# Adafruit_EZ-SFX_with_Amp.net
KiCad netlist of a schematic drawn in EAGLE
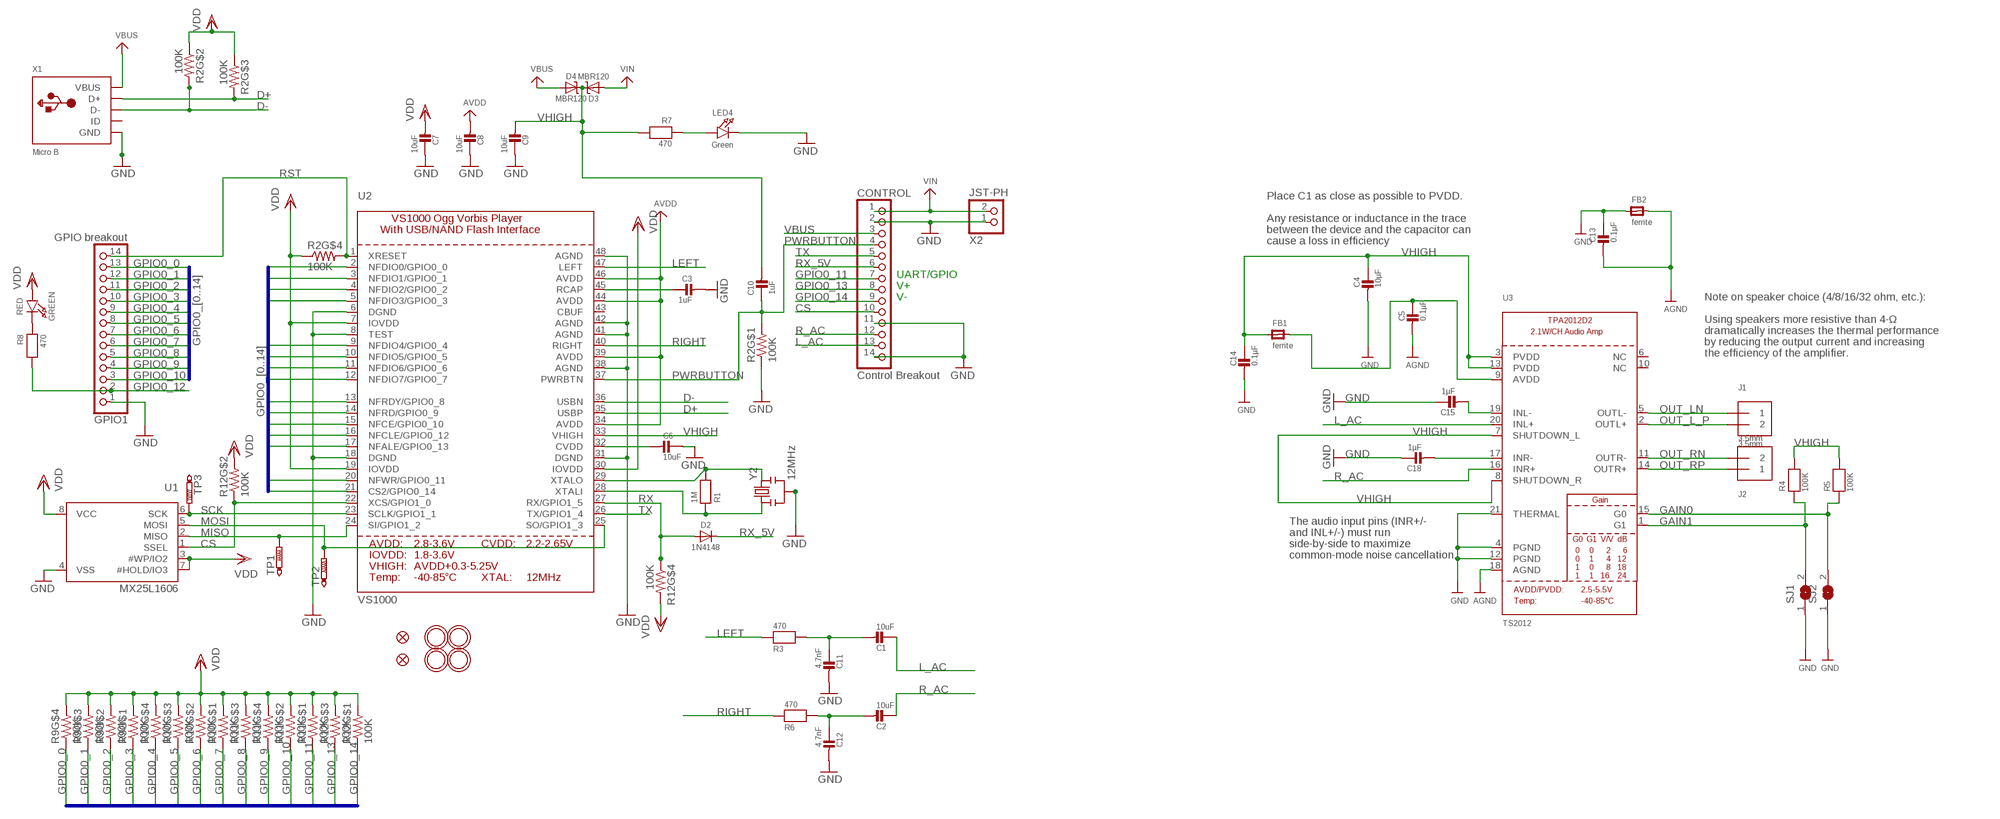
[diagram p0: schematic, sheet 1]

(export (version "E")
  (design (tool "Eeschema 10.0.6"))
  (components
    (comp (ref "C1")
      (value "10uF")
      (footprint "eagle-import:0805-NO")
      (libsource (lib "eagle-import") (part "CAP_CERAMIC0805-NOOUTLINE"))
    )
    (comp (ref "C2")
      (value "10uF")
      (footprint "eagle-import:0805_10MGAP")
      (libsource (lib "eagle-import") (part "CAP_CERAMIC0805_10MGAP"))
    )
    (comp (ref "C3")
      (value "1uF")
      (footprint "eagle-import:0805-NO")
      (libsource (lib "eagle-import") (part "CAP_CERAMIC0805-NOOUTLINE"))
    )
    (comp (ref "C4")
      (value "10µF")
      (footprint "eagle-import:0805-NO")
      (libsource (lib "eagle-import") (part "CAP_CERAMIC0805-NOOUTLINE"))
    )
    (comp (ref "C5")
      (value "0.1µF")
      (footprint "eagle-import:0805-NO")
      (libsource (lib "eagle-import") (part "CAP_CERAMIC0805-NOOUTLINE"))
    )
    (comp (ref "C6")
      (value "10uF")
      (footprint "eagle-import:0805_10MGAP")
      (libsource (lib "eagle-import") (part "CAP_CERAMIC0805_10MGAP"))
    )
    (comp (ref "C7")
      (value "10uF")
      (footprint "eagle-import:0805_10MGAP")
      (libsource (lib "eagle-import") (part "CAP_CERAMIC0805_10MGAP"))
    )
    (comp (ref "C8")
      (value "10uF")
      (footprint "eagle-import:0805-NO")
      (libsource (lib "eagle-import") (part "CAP_CERAMIC0805-NOOUTLINE"))
    )
    (comp (ref "C9")
      (value "10uF")
      (footprint "eagle-import:0805-NO")
      (libsource (lib "eagle-import") (part "CAP_CERAMIC0805-NOOUTLINE"))
    )
    (comp (ref "C10")
      (value "1uF")
      (footprint "eagle-import:0805-NO")
      (libsource (lib "eagle-import") (part "CAP_CERAMIC0805-NOOUTLINE"))
    )
    (comp (ref "C11")
      (value "4.7nF")
      (footprint "eagle-import:0805-NO")
      (libsource (lib "eagle-import") (part "CAP_CERAMIC0805-NOOUTLINE"))
    )
    (comp (ref "C12")
      (value "4.7nF")
      (footprint "eagle-import:0805-NO")
      (libsource (lib "eagle-import") (part "CAP_CERAMIC0805-NOOUTLINE"))
    )
    (comp (ref "C13")
      (value "0.1µF")
      (footprint "eagle-import:0805-NO")
      (libsource (lib "eagle-import") (part "CAP_CERAMIC0805-NOOUTLINE"))
    )
    (comp (ref "C14")
      (value "0.1µF")
      (footprint "eagle-import:0805-NO")
      (libsource (lib "eagle-import") (part "CAP_CERAMIC0805-NOOUTLINE"))
    )
    (comp (ref "C15")
      (value "1µF")
      (footprint "eagle-import:0805-NO")
      (libsource (lib "eagle-import") (part "CAP_CERAMIC0805-NOOUTLINE"))
    )
    (comp (ref "C18")
      (value "1µF")
      (footprint "eagle-import:0805-NO")
      (libsource (lib "eagle-import") (part "CAP_CERAMIC0805-NOOUTLINE"))
    )
    (comp (ref "CONTROL")
      (value "Control Breakout")
      (footprint "eagle-import:1X14-CB")
      (libsource (lib "eagle-import") (part "PINHD-1X14-CB"))
    )
    (comp (ref "D2")
      (value "1N4148")
      (footprint "eagle-import:SOD-323")
      (libsource (lib "eagle-import") (part "DIODESOD-323"))
    )
    (comp (ref "D3")
      (value "MBR120")
      (footprint "eagle-import:SOD-123")
      (libsource (lib "eagle-import") (part "DIODE-SCHOTTKYSOD-123"))
    )
    (comp (ref "D4")
      (value "MBR120")
      (footprint "eagle-import:SOD-123")
      (libsource (lib "eagle-import") (part "DIODE-SCHOTTKYSOD-123"))
    )
    (comp (ref "FB1")
      (value "ferrite")
      (footprint "eagle-import:_0805MP")
      (libsource (lib "eagle-import") (part "FERRITE_0805MP"))
    )
    (comp (ref "FB2")
      (value "ferrite")
      (footprint "eagle-import:_0805MP")
      (libsource (lib "eagle-import") (part "FERRITE_0805MP"))
    )
    (comp (ref "FID1")
      (value "FIDUCIAL\"\"")
      (footprint "eagle-import:FIDUCIAL_1MM")
      (libsource (lib "eagle-import") (part "FIDUCIAL{dblquote}{dblquote}"))
    )
    (comp (ref "FID2")
      (value "FIDUCIAL\"\"")
      (footprint "eagle-import:FIDUCIAL_1MM")
      (libsource (lib "eagle-import") (part "FIDUCIAL{dblquote}{dblquote}"))
    )
    (comp (ref "GPIO1")
      (value "GPIO breakout")
      (footprint "eagle-import:1X14-CB")
      (libsource (lib "eagle-import") (part "PINHD-1X14-CB"))
    )
    (comp (ref "GREEN")
      (value "RED")
      (footprint "eagle-import:CHIPLED_0805_NOOUTLINE")
      (libsource (lib "eagle-import") (part "LED0805_NOOUTLINE"))
    )
    (comp (ref "J1")
      (value "3.5mm")
      (footprint "eagle-import:TERMBLOCK_1X2-3.5MM")
      (libsource (lib "eagle-import") (part "TERMBLOCK_1X2"))
    )
    (comp (ref "J2")
      (value "3.5mm")
      (footprint "eagle-import:TERMBLOCK_1X2-3.5MM")
      (libsource (lib "eagle-import") (part "TERMBLOCK_1X2"))
    )
    (comp (ref "LED4")
      (value "Green")
      (footprint "eagle-import:CHIPLED_0805_NOOUTLINE")
      (libsource (lib "eagle-import") (part "LED0805_NOOUTLINE"))
    )
    (comp (ref "R1")
      (value "1M")
      (footprint "eagle-import:0805-NO")
      (libsource (lib "eagle-import") (part "RESISTOR0805_NOOUTLINE"))
    )
    (comp (ref "R2")
      (value "100K")
      (footprint "eagle-import:RESPACK_4X0603")
      (libsource (lib "eagle-import") (part "RESISTOR_4PACK_US"))
    )
    (comp (ref "R3")
      (value "470")
      (footprint "eagle-import:0805-NO")
      (libsource (lib "eagle-import") (part "RESISTOR0805_NOOUTLINE"))
    )
    (comp (ref "R4")
      (value "100K")
      (footprint "eagle-import:0805-NO")
      (libsource (lib "eagle-import") (part "RESISTOR0805_NOOUTLINE"))
    )
    (comp (ref "R5")
      (value "100K")
      (footprint "eagle-import:0805-NO")
      (libsource (lib "eagle-import") (part "RESISTOR0805_NOOUTLINE"))
    )
    (comp (ref "R6")
      (value "470")
      (footprint "eagle-import:0805-NO")
      (libsource (lib "eagle-import") (part "RESISTOR0805_NOOUTLINE"))
    )
    (comp (ref "R7")
      (value "470")
      (footprint "eagle-import:0805-NO")
      (libsource (lib "eagle-import") (part "RESISTOR0805_NOOUTLINE"))
    )
    (comp (ref "R8")
      (value "470")
      (footprint "eagle-import:0805-NO")
      (libsource (lib "eagle-import") (part "RESISTOR0805_NOOUTLINE"))
    )
    (comp (ref "R9")
      (value "100K")
      (footprint "eagle-import:RESPACK_4X0603")
      (libsource (lib "eagle-import") (part "RESISTOR_4PACK_US"))
    )
    (comp (ref "R10")
      (value "100K")
      (footprint "eagle-import:RESPACK_4X0603")
      (libsource (lib "eagle-import") (part "RESISTOR_4PACK_US"))
    )
    (comp (ref "R11")
      (value "100K")
      (footprint "eagle-import:RESPACK_4X0603")
      (libsource (lib "eagle-import") (part "RESISTOR_4PACK_US"))
    )
    (comp (ref "R12")
      (value "100K")
      (footprint "eagle-import:RESPACK_4X0603")
      (libsource (lib "eagle-import") (part "RESISTOR_4PACK_US"))
    )
    (comp (ref "SJ1")
      (value "SOLDERJUMPER")
      (footprint "eagle-import:SOLDERJUMPER_ARROW_NOPASTE")
      (libsource (lib "eagle-import") (part "SOLDERJUMPER"))
    )
    (comp (ref "SJ2")
      (value "SOLDERJUMPERCLOSED")
      (footprint "eagle-import:SOLDERJUMPER_CLOSEDWIRE")
      (libsource (lib "eagle-import") (part "SOLDERJUMPERCLOSED"))
    )
    (comp (ref "TP1")
      (value "PTR1B1,27")
      (footprint "eagle-import:B1,27")
      (libsource (lib "eagle-import") (part "PTR1B1,27"))
    )
    (comp (ref "TP2")
      (value "PTR1B1,27")
      (footprint "eagle-import:B1,27")
      (libsource (lib "eagle-import") (part "PTR1B1,27"))
    )
    (comp (ref "TP3")
      (value "PTR1B1,27")
      (footprint "eagle-import:B1,27")
      (libsource (lib "eagle-import") (part "PTR1B1,27"))
    )
    (comp (ref "U$5")
      (value "MOUNTINGHOLE2.5")
      (footprint "eagle-import:MOUNTINGHOLE_2.5_PLATED")
      (libsource (lib "eagle-import") (part "MOUNTINGHOLE2.5"))
    )
    (comp (ref "U$6")
      (value "MOUNTINGHOLE2.5")
      (footprint "eagle-import:MOUNTINGHOLE_2.5_PLATED")
      (libsource (lib "eagle-import") (part "MOUNTINGHOLE2.5"))
    )
    (comp (ref "U$7")
      (value "MOUNTINGHOLE2.5")
      (footprint "eagle-import:MOUNTINGHOLE_2.5_PLATED")
      (libsource (lib "eagle-import") (part "MOUNTINGHOLE2.5"))
    )
    (comp (ref "U$8")
      (value "MOUNTINGHOLE2.5")
      (footprint "eagle-import:MOUNTINGHOLE_2.5_PLATED")
      (libsource (lib "eagle-import") (part "MOUNTINGHOLE2.5"))
    )
    (comp (ref "U1")
      (value "MX25L1606")
      (footprint "eagle-import:SOIC8_208MIL")
      (libsource (lib "eagle-import") (part "SPIFLASH_SOIC8208MIL"))
    )
    (comp (ref "U2")
      (value "VS1000")
      (footprint "eagle-import:LQFP48")
      (libsource (lib "eagle-import") (part "VS1000"))
    )
    (comp (ref "U3")
      (value "TS2012")
      (footprint "eagle-import:WQFN20")
      (libsource (lib "eagle-import") (part "AUDIOAMP_TPA2012D2"))
    )
    (comp (ref "X1")
      (value "Micro B")
      (footprint "eagle-import:4UCONN_20329")
      (libsource (lib "eagle-import") (part "USBMICRO_20329"))
    )
    (comp (ref "X2")
      (value "JST-PH")
      (footprint "eagle-import:JSTPH2")
      (libsource (lib "eagle-import") (part "CON_JST_PH_2PIN"))
    )
    (comp (ref "Y2")
      (value "12MHz")
      (footprint "eagle-import:RESONATOR-SMD")
      (libsource (lib "eagle-import") (part "RESONATORSMD"))
    )
  )
  (nets
    (net (code "1") (name "/CS") (class "Default")
      (node (ref "CONTROL") (pin "10") (pinfunction "10_10") (pintype "passive"))
      (node (ref "R12") (pin "2") (pinfunction "1_2") (pintype "passive"))
      (node (ref "U1") (pin "1") (pinfunction "SSEL_1") (pintype "bidirectional"))
      (node (ref "U2") (pin "22") (pinfunction "XCS/GPIO1_0_22") (pintype "bidirectional"))
    )
    (net (code "2") (name "/D+") (class "Default")
      (node (ref "R2") (pin "6") (pinfunction "2_6") (pintype "passive"))
      (node (ref "U2") (pin "35") (pinfunction "USBP_35") (pintype "bidirectional"))
      (node (ref "X1") (pin "D+") (pinfunction "D+_D+") (pintype "bidirectional"))
    )
    (net (code "3") (name "/D-") (class "Default")
      (node (ref "R2") (pin "7") (pinfunction "2_7") (pintype "passive"))
      (node (ref "U2") (pin "36") (pinfunction "USBN_36") (pintype "bidirectional"))
      (node (ref "X1") (pin "D-") (pinfunction "D-_D-") (pintype "bidirectional"))
    )
    (net (code "4") (name "/GAIN0") (class "Default")
      (node (ref "R5") (pin "1") (pinfunction "1_1") (pintype "passive"))
      (node (ref "SJ2") (pin "2") (pinfunction "2_2") (pintype "passive"))
      (node (ref "U3") (pin "15") (pinfunction "G0_15") (pintype "input"))
    )
    (net (code "5") (name "/GAIN1") (class "Default")
      (node (ref "R4") (pin "1") (pinfunction "1_1") (pintype "passive"))
      (node (ref "SJ1") (pin "2") (pinfunction "2_2") (pintype "passive"))
      (node (ref "U3") (pin "1") (pinfunction "G1_1") (pintype "input"))
    )
    (net (code "6") (name "/GPIO0_0") (class "Default")
      (node (ref "GPIO1") (pin "13") (pinfunction "13_13") (pintype "passive"))
      (node (ref "R9") (pin "4") (pinfunction "1_4") (pintype "passive"))
      (node (ref "U2") (pin "2") (pinfunction "NFDIO0/GPIO0_0_2") (pintype "bidirectional"))
    )
    (net (code "7") (name "/GPIO0_1") (class "Default")
      (node (ref "GPIO1") (pin "12") (pinfunction "12_12") (pintype "passive"))
      (node (ref "R9") (pin "3") (pinfunction "1_3") (pintype "passive"))
      (node (ref "U2") (pin "3") (pinfunction "NFDIO1/GPIO0_1_3") (pintype "bidirectional"))
    )
    (net (code "8") (name "/GPIO0_2") (class "Default")
      (node (ref "GPIO1") (pin "11") (pinfunction "11_11") (pintype "passive"))
      (node (ref "R9") (pin "2") (pinfunction "1_2") (pintype "passive"))
      (node (ref "U2") (pin "4") (pinfunction "NFDIO2/GPIO0_2_4") (pintype "bidirectional"))
    )
    (net (code "9") (name "/GPIO0_3") (class "Default")
      (node (ref "GPIO1") (pin "10") (pinfunction "10_10") (pintype "passive"))
      (node (ref "R9") (pin "1") (pinfunction "1_1") (pintype "passive"))
      (node (ref "U2") (pin "5") (pinfunction "NFDIO3/GPIO0_3_5") (pintype "bidirectional"))
    )
    (net (code "10") (name "/GPIO0_4") (class "Default")
      (node (ref "GPIO1") (pin "9") (pinfunction "9_9") (pintype "passive"))
      (node (ref "R10") (pin "4") (pinfunction "1_4") (pintype "passive"))
      (node (ref "U2") (pin "9") (pinfunction "NFDIO4/GPIO0_4_9") (pintype "bidirectional"))
    )
    (net (code "11") (name "/GPIO0_5") (class "Default")
      (node (ref "GPIO1") (pin "8") (pinfunction "8_8") (pintype "passive"))
      (node (ref "R10") (pin "3") (pinfunction "1_3") (pintype "passive"))
      (node (ref "U2") (pin "10") (pinfunction "NFDIO5/GPIO0_5_10") (pintype "bidirectional"))
    )
    (net (code "12") (name "/GPIO0_6") (class "Default")
      (node (ref "GPIO1") (pin "7") (pinfunction "7_7") (pintype "passive"))
      (node (ref "R10") (pin "2") (pinfunction "1_2") (pintype "passive"))
      (node (ref "U2") (pin "11") (pinfunction "NFDIO6/GPIO0_6_11") (pintype "bidirectional"))
    )
    (net (code "13") (name "/GPIO0_7") (class "Default")
      (node (ref "GPIO1") (pin "6") (pinfunction "6_6") (pintype "passive"))
      (node (ref "R10") (pin "1") (pinfunction "1_1") (pintype "passive"))
      (node (ref "U2") (pin "12") (pinfunction "NFDIO7/GPIO0_7_12") (pintype "bidirectional"))
    )
    (net (code "14") (name "/GPIO0_8") (class "Default")
      (node (ref "GPIO1") (pin "5") (pinfunction "5_5") (pintype "passive"))
      (node (ref "R11") (pin "3") (pinfunction "1_3") (pintype "passive"))
      (node (ref "U2") (pin "13") (pinfunction "NFRDY/GPIO0_8_13") (pintype "bidirectional"))
    )
    (net (code "15") (name "/GPIO0_9") (class "Default")
      (node (ref "GPIO1") (pin "4") (pinfunction "4_4") (pintype "passive"))
      (node (ref "R11") (pin "4") (pinfunction "1_4") (pintype "passive"))
      (node (ref "U2") (pin "14") (pinfunction "NFRD/GPIO0_9_14") (pintype "bidirectional"))
    )
    (net (code "16") (name "/GPIO0_10") (class "Default")
      (node (ref "GPIO1") (pin "3") (pinfunction "3_3") (pintype "passive"))
      (node (ref "R11") (pin "2") (pinfunction "1_2") (pintype "passive"))
      (node (ref "U2") (pin "15") (pinfunction "NFCE/GPIO0_10_15") (pintype "bidirectional"))
    )
    (net (code "17") (name "/GPIO0_11") (class "Default")
      (node (ref "CONTROL") (pin "7") (pinfunction "7_7") (pintype "passive"))
      (node (ref "R11") (pin "1") (pinfunction "1_1") (pintype "passive"))
      (node (ref "U2") (pin "20") (pinfunction "NFWR/GPIO0_11_20") (pintype "bidirectional"))
    )
    (net (code "18") (name "/GPIO0_12") (class "Default")
      (node (ref "GPIO1") (pin "2") (pinfunction "2_2") (pintype "passive"))
      (node (ref "R8") (pin "2") (pinfunction "2_2") (pintype "passive"))
      (node (ref "U2") (pin "16") (pinfunction "NFCLE/GPIO0_12_16") (pintype "bidirectional"))
    )
    (net (code "19") (name "/GPIO0_13") (class "Default")
      (node (ref "CONTROL") (pin "8") (pinfunction "8_8") (pintype "passive"))
      (node (ref "R12") (pin "3") (pinfunction "1_3") (pintype "passive"))
      (node (ref "U2") (pin "17") (pinfunction "NFALE/GPIO0_13_17") (pintype "bidirectional"))
    )
    (net (code "20") (name "/GPIO0_14") (class "Default")
      (node (ref "CONTROL") (pin "9") (pinfunction "9_9") (pintype "passive"))
      (node (ref "R12") (pin "1") (pinfunction "1_1") (pintype "passive"))
      (node (ref "U2") (pin "21") (pinfunction "CS2/GPIO0_14_21") (pintype "bidirectional"))
    )
    (net (code "22") (name "/LEFT") (class "Default")
      (node (ref "R3") (pin "1") (pinfunction "1_1") (pintype "passive"))
      (node (ref "U2") (pin "47") (pinfunction "LEFT_47") (pintype "bidirectional"))
    )
    (net (code "23") (name "/L_AC") (class "Default")
      (node (ref "C1") (pin "1") (pinfunction "1_1") (pintype "passive"))
      (node (ref "CONTROL") (pin "13") (pinfunction "13_13") (pintype "passive"))
      (node (ref "U3") (pin "20") (pinfunction "INL+_20") (pintype "input"))
    )
    (net (code "24") (name "/MISO") (class "Default")
      (node (ref "TP1") (pin "TP") (pinfunction "TP_TP") (pintype "input"))
      (node (ref "U1") (pin "2") (pinfunction "MISO_2") (pintype "bidirectional"))
      (node (ref "U2") (pin "24") (pinfunction "SI/GPIO1_2_24") (pintype "bidirectional"))
    )
    (net (code "25") (name "/MOSI") (class "Default")
      (node (ref "TP2") (pin "TP") (pinfunction "TP_TP") (pintype "input"))
      (node (ref "U1") (pin "5") (pinfunction "MOSI_5") (pintype "bidirectional"))
      (node (ref "U2") (pin "25") (pinfunction "SO/GPIO1_3_25") (pintype "bidirectional"))
    )
    (net (code "26") (name "/OUT_LN") (class "Default")
      (node (ref "J1") (pin "1") (pinfunction "1_1") (pintype "passive"))
      (node (ref "U3") (pin "5") (pinfunction "OUTL-_5") (pintype "output"))
    )
    (net (code "27") (name "/OUT_L_P") (class "Default")
      (node (ref "J1") (pin "2") (pinfunction "2_2") (pintype "passive"))
      (node (ref "U3") (pin "2") (pinfunction "OUTL+_2") (pintype "output"))
    )
    (net (code "28") (name "/OUT_RN") (class "Default")
      (node (ref "J2") (pin "2") (pinfunction "2_2") (pintype "passive"))
      (node (ref "U3") (pin "11") (pinfunction "OUTR-_11") (pintype "output"))
    )
    (net (code "29") (name "/OUT_RP") (class "Default")
      (node (ref "J2") (pin "1") (pinfunction "1_1") (pintype "passive"))
      (node (ref "U3") (pin "14") (pinfunction "OUTR+_14") (pintype "output"))
    )
    (net (code "30") (name "/PWRBUTTON") (class "Default")
      (node (ref "C10") (pin "1") (pinfunction "1_1") (pintype "passive"))
      (node (ref "CONTROL") (pin "4") (pinfunction "4_4") (pintype "passive"))
      (node (ref "R2") (pin "8") (pinfunction "2_8") (pintype "passive"))
      (node (ref "U2") (pin "37") (pinfunction "PWRBTN_37") (pintype "bidirectional"))
    )
    (net (code "31") (name "/RIGHT") (class "Default")
      (node (ref "R6") (pin "1") (pinfunction "1_1") (pintype "passive"))
      (node (ref "U2") (pin "40") (pinfunction "RIGHT_40") (pintype "bidirectional"))
    )
    (net (code "32") (name "/RST") (class "Default")
      (node (ref "GPIO1") (pin "14") (pinfunction "14_14") (pintype "passive"))
      (node (ref "R2") (pin "5") (pinfunction "2_5") (pintype "passive"))
      (node (ref "U2") (pin "1") (pinfunction "XRESET_1") (pintype "bidirectional"))
    )
    (net (code "33") (name "/RX") (class "Default")
      (node (ref "D2") (pin "A") (pinfunction "A_A") (pintype "passive"))
      (node (ref "R12") (pin "4") (pinfunction "1_4") (pintype "passive"))
      (node (ref "U2") (pin "27") (pinfunction "RX/GPIO1_5_27") (pintype "bidirectional"))
    )
    (net (code "34") (name "/RX_5V") (class "Default")
      (node (ref "CONTROL") (pin "6") (pinfunction "6_6") (pintype "passive"))
      (node (ref "D2") (pin "C") (pinfunction "C_C") (pintype "passive"))
    )
    (net (code "35") (name "/R_AC") (class "Default")
      (node (ref "C2") (pin "1") (pinfunction "1_1") (pintype "passive"))
      (node (ref "CONTROL") (pin "12") (pinfunction "12_12") (pintype "passive"))
      (node (ref "U3") (pin "16") (pinfunction "INR+_16") (pintype "input"))
    )
    (net (code "36") (name "/SCK") (class "Default")
      (node (ref "TP3") (pin "TP") (pinfunction "TP_TP") (pintype "input"))
      (node (ref "U1") (pin "6") (pinfunction "SCK_6") (pintype "bidirectional"))
      (node (ref "U2") (pin "23") (pinfunction "SCLK/GPIO1_1_23") (pintype "bidirectional"))
    )
    (net (code "37") (name "/TX") (class "Default")
      (node (ref "CONTROL") (pin "5") (pinfunction "5_5") (pintype "passive"))
      (node (ref "U2") (pin "26") (pinfunction "TX/GPIO1_4_26") (pintype "bidirectional"))
    )
    (net (code "38") (name "/VHIGH") (class "Default")
      (node (ref "C10") (pin "2") (pinfunction "2_2") (pintype "passive"))
      (node (ref "C14") (pin "1") (pinfunction "1_1") (pintype "passive"))
      (node (ref "C4") (pin "1") (pinfunction "1_1") (pintype "passive"))
      (node (ref "C9") (pin "2") (pinfunction "2_2") (pintype "passive"))
      (node (ref "D3") (pin "C") (pinfunction "C_C") (pintype "passive"))
      (node (ref "D4") (pin "C") (pinfunction "C_C") (pintype "passive"))
      (node (ref "FB1") (pin "1") (pinfunction "P$1_1") (pintype "passive"))
      (node (ref "R4") (pin "2") (pinfunction "2_2") (pintype "passive"))
      (node (ref "R5") (pin "2") (pinfunction "2_2") (pintype "passive"))
      (node (ref "R7") (pin "2") (pinfunction "2_2") (pintype "passive"))
      (node (ref "U2") (pin "33") (pinfunction "VHIGH_33") (pintype "power_in"))
      (node (ref "U3") (pin "13") (pinfunction "PVDD_13") (pintype "power_in"))
      (node (ref "U3") (pin "3") (pinfunction "PVDD_3") (pintype "power_in"))
      (node (ref "U3") (pin "7") (pinfunction "SHUTDOWN_L_7") (pintype "input"))
      (node (ref "U3") (pin "8") (pinfunction "SHUTDOWN_R_8") (pintype "input"))
    )
    (net (code "39") (name "AGND") (class "Default")
      (node (ref "C13") (pin "2") (pinfunction "2_2") (pintype "passive"))
      (node (ref "C5") (pin "2") (pinfunction "2_2") (pintype "passive"))
      (node (ref "FB2") (pin "2") (pinfunction "P$2_2") (pintype "passive"))
      (node (ref "U3") (pin "18") (pinfunction "AGND_18") (pintype "power_in"))
    )
    (net (code "40") (name "AVDD") (class "Default")
      (node (ref "C8") (pin "2") (pinfunction "2_2") (pintype "passive"))
      (node (ref "U2") (pin "34") (pinfunction "AVDD_34") (pintype "power_in"))
      (node (ref "U2") (pin "39") (pinfunction "AVDD_39") (pintype "power_in"))
      (node (ref "U2") (pin "44") (pinfunction "AVDD_44") (pintype "power_in"))
      (node (ref "U2") (pin "46") (pinfunction "AVDD_46") (pintype "power_in"))
    )
    (net (code "41") (name "GND") (class "Default")
      (node (ref "C11") (pin "2") (pinfunction "2_2") (pintype "passive"))
      (node (ref "C12") (pin "2") (pinfunction "2_2") (pintype "passive"))
      (node (ref "C13") (pin "1") (pinfunction "1_1") (pintype "passive"))
      (node (ref "C14") (pin "2") (pinfunction "2_2") (pintype "passive"))
      (node (ref "C15") (pin "1") (pinfunction "1_1") (pintype "passive"))
      (node (ref "C18") (pin "1") (pinfunction "1_1") (pintype "passive"))
      (node (ref "C3") (pin "2") (pinfunction "2_2") (pintype "passive"))
      (node (ref "C4") (pin "2") (pinfunction "2_2") (pintype "passive"))
      (node (ref "C6") (pin "1") (pinfunction "1_1") (pintype "passive"))
      (node (ref "C7") (pin "1") (pinfunction "1_1") (pintype "passive"))
      (node (ref "C8") (pin "1") (pinfunction "1_1") (pintype "passive"))
      (node (ref "C9") (pin "1") (pinfunction "1_1") (pintype "passive"))
      (node (ref "CONTROL") (pin "11") (pinfunction "11_11") (pintype "passive"))
      (node (ref "CONTROL") (pin "14") (pinfunction "14_14") (pintype "passive"))
      (node (ref "CONTROL") (pin "2") (pinfunction "2_2") (pintype "passive"))
      (node (ref "FB2") (pin "1") (pinfunction "P$1_1") (pintype "passive"))
      (node (ref "GPIO1") (pin "1") (pinfunction "1_1") (pintype "passive"))
      (node (ref "LED4") (pin "C") (pinfunction "C_C") (pintype "passive"))
      (node (ref "R2") (pin "1") (pinfunction "1_1") (pintype "passive"))
      (node (ref "SJ1") (pin "1") (pinfunction "1_1") (pintype "passive"))
      (node (ref "SJ2") (pin "1") (pinfunction "1_1") (pintype "passive"))
      (node (ref "U1") (pin "4") (pinfunction "VSS_4") (pintype "bidirectional"))
      (node (ref "U2") (pin "18") (pinfunction "DGND_18") (pintype "power_in"))
      (node (ref "U2") (pin "31") (pinfunction "DGND_31") (pintype "power_in"))
      (node (ref "U2") (pin "38") (pinfunction "AGND_38") (pintype "power_in"))
      (node (ref "U2") (pin "41") (pinfunction "AGND_41") (pintype "power_in"))
      (node (ref "U2") (pin "42") (pinfunction "AGND_42") (pintype "power_in"))
      (node (ref "U2") (pin "48") (pinfunction "AGND_48") (pintype "power_in"))
      (node (ref "U2") (pin "6") (pinfunction "DGND_6") (pintype "power_in"))
      (node (ref "U2") (pin "8") (pinfunction "TEST_8") (pintype "bidirectional"))
      (node (ref "U3") (pin "12") (pinfunction "PGND_12") (pintype "power_in"))
      (node (ref "U3") (pin "21") (pinfunction "THERMAL_21") (pintype "bidirectional"))
      (node (ref "U3") (pin "4") (pinfunction "PGND_4") (pintype "power_in"))
      (node (ref "X1") (pin "BASE@1") (pinfunction "GND_BASE@1") (pintype "power_in"))
      (node (ref "X1") (pin "BASE@2") (pinfunction "GND_BASE@2") (pintype "power_in"))
      (node (ref "X1") (pin "GND") (pinfunction "GND_GND") (pintype "power_in"))
      (node (ref "X1") (pin "SPRT@1") (pinfunction "GND_SPRT@1") (pintype "power_in"))
      (node (ref "X1") (pin "SPRT@2") (pinfunction "GND_SPRT@2") (pintype "power_in"))
      (node (ref "X1") (pin "SPRT@3") (pinfunction "GND_SPRT@3") (pintype "power_in"))
      (node (ref "X1") (pin "SPRT@4") (pinfunction "GND_SPRT@4") (pintype "power_in"))
      (node (ref "X2") (pin "1") (pinfunction "1_1") (pintype "passive"))
      (node (ref "Y2") (pin "2") (pinfunction "2_2") (pintype "passive"))
    )
    (net (code "42") (name "Net-(C1-Pad2)") (class "Default")
      (node (ref "C1") (pin "2") (pinfunction "2_2") (pintype "passive"))
      (node (ref "C11") (pin "1") (pinfunction "1_1") (pintype "passive"))
      (node (ref "R3") (pin "2") (pinfunction "2_2") (pintype "passive"))
    )
    (net (code "43") (name "Net-(C12-Pad1)") (class "Default")
      (node (ref "C12") (pin "1") (pinfunction "1_1") (pintype "passive"))
      (node (ref "C2") (pin "2") (pinfunction "2_2") (pintype "passive"))
      (node (ref "R6") (pin "2") (pinfunction "2_2") (pintype "passive"))
    )
    (net (code "44") (name "Net-(FB1-P$2)") (class "Default")
      (node (ref "C5") (pin "1") (pinfunction "1_1") (pintype "passive"))
      (node (ref "FB1") (pin "2") (pinfunction "P$2_2") (pintype "passive"))
      (node (ref "U3") (pin "9") (pinfunction "AVDD_9") (pintype "power_in"))
    )
    (net (code "45") (name "Net-(GREEN-PadC)") (class "Default")
      (node (ref "GREEN") (pin "C") (pinfunction "C_C") (pintype "passive"))
      (node (ref "R8") (pin "1") (pinfunction "1_1") (pintype "passive"))
    )
    (net (code "46") (name "Net-(LED4-PadA)") (class "Default")
      (node (ref "LED4") (pin "A") (pinfunction "A_A") (pintype "passive"))
      (node (ref "R7") (pin "1") (pinfunction "1_1") (pintype "passive"))
    )
    (net (code "47") (name "Net-(U2-CVDD)") (class "Default")
      (node (ref "C6") (pin "2") (pinfunction "2_2") (pintype "passive"))
      (node (ref "U2") (pin "32") (pinfunction "CVDD_32") (pintype "power_in"))
    )
    (net (code "48") (name "Net-(U2-RCAP)") (class "Default")
      (node (ref "C3") (pin "1") (pinfunction "1_1") (pintype "passive"))
      (node (ref "U2") (pin "45") (pinfunction "RCAP_45") (pintype "bidirectional"))
    )
    (net (code "49") (name "Net-(U2-XTALI)") (class "Default")
      (node (ref "R1") (pin "1") (pinfunction "1_1") (pintype "passive"))
      (node (ref "U2") (pin "28") (pinfunction "XTALI_28") (pintype "bidirectional"))
      (node (ref "Y2") (pin "1") (pinfunction "1_1") (pintype "passive"))
    )
    (net (code "50") (name "Net-(U2-XTALO)") (class "Default")
      (node (ref "R1") (pin "2") (pinfunction "2_2") (pintype "passive"))
      (node (ref "U2") (pin "29") (pinfunction "XTALO_29") (pintype "bidirectional"))
      (node (ref "Y2") (pin "3") (pinfunction "3_3") (pintype "passive"))
    )
    (net (code "51") (name "Net-(U3-INL-)") (class "Default")
      (node (ref "C15") (pin "2") (pinfunction "2_2") (pintype "passive"))
      (node (ref "U3") (pin "19") (pinfunction "INL-_19") (pintype "input"))
    )
    (net (code "52") (name "Net-(U3-INR-)") (class "Default")
      (node (ref "C18") (pin "2") (pinfunction "2_2") (pintype "passive"))
      (node (ref "U3") (pin "17") (pinfunction "INR-_17") (pintype "input"))
    )
    (net (code "53") (name "VBUS") (class "Default")
      (node (ref "CONTROL") (pin "3") (pinfunction "3_3") (pintype "passive"))
      (node (ref "D4") (pin "A") (pinfunction "A_A") (pintype "passive"))
      (node (ref "X1") (pin "VBUS") (pinfunction "VBUS_VBUS") (pintype "power_in"))
    )
    (net (code "54") (name "VDD") (class "Default")
      (node (ref "C7") (pin "2") (pinfunction "2_2") (pintype "passive"))
      (node (ref "GREEN") (pin "A") (pinfunction "A_A") (pintype "passive"))
      (node (ref "R10") (pin "5") (pinfunction "2_5") (pintype "passive"))
      (node (ref "R10") (pin "6") (pinfunction "2_6") (pintype "passive"))
      (node (ref "R10") (pin "7") (pinfunction "2_7") (pintype "passive"))
      (node (ref "R10") (pin "8") (pinfunction "2_8") (pintype "passive"))
      (node (ref "R11") (pin "5") (pinfunction "2_5") (pintype "passive"))
      (node (ref "R11") (pin "6") (pinfunction "2_6") (pintype "passive"))
      (node (ref "R11") (pin "7") (pinfunction "2_7") (pintype "passive"))
      (node (ref "R11") (pin "8") (pinfunction "2_8") (pintype "passive"))
      (node (ref "R12") (pin "5") (pinfunction "2_5") (pintype "passive"))
      (node (ref "R12") (pin "6") (pinfunction "2_6") (pintype "passive"))
      (node (ref "R12") (pin "7") (pinfunction "2_7") (pintype "passive"))
      (node (ref "R12") (pin "8") (pinfunction "2_8") (pintype "passive"))
      (node (ref "R2") (pin "2") (pinfunction "1_2") (pintype "passive"))
      (node (ref "R2") (pin "3") (pinfunction "1_3") (pintype "passive"))
      (node (ref "R2") (pin "4") (pinfunction "1_4") (pintype "passive"))
      (node (ref "R9") (pin "5") (pinfunction "2_5") (pintype "passive"))
      (node (ref "R9") (pin "6") (pinfunction "2_6") (pintype "passive"))
      (node (ref "R9") (pin "7") (pinfunction "2_7") (pintype "passive"))
      (node (ref "R9") (pin "8") (pinfunction "2_8") (pintype "passive"))
      (node (ref "U1") (pin "3") (pinfunction "#WP/IO2_3") (pintype "bidirectional"))
      (node (ref "U1") (pin "7") (pinfunction "#HOLD/IO3_7") (pintype "bidirectional"))
      (node (ref "U1") (pin "8") (pinfunction "VCC_8") (pintype "bidirectional"))
      (node (ref "U2") (pin "19") (pinfunction "IOVDD_19") (pintype "power_in"))
      (node (ref "U2") (pin "30") (pinfunction "IOVDD_30") (pintype "power_in"))
      (node (ref "U2") (pin "7") (pinfunction "IOVDD_7") (pintype "power_in"))
    )
    (net (code "55") (name "VIN") (class "Default")
      (node (ref "CONTROL") (pin "1") (pinfunction "1_1") (pintype "passive"))
      (node (ref "D3") (pin "A") (pinfunction "A_A") (pintype "passive"))
      (node (ref "X2") (pin "2") (pinfunction "2_2") (pintype "passive"))
    )
    (net (code "56") (name "unconnected-(U2-CBUF-Pad43)") (class "Default")
      (node (ref "U2") (pin "43") (pinfunction "CBUF_43") (pintype "bidirectional"))
    )
    (net (code "57") (name "unconnected-(U3-NC-Pad6)") (class "Default")
      (node (ref "U3") (pin "6") (pinfunction "NC_6") (pintype "no_connect"))
    )
    (net (code "58") (name "unconnected-(U3-NC-Pad10)") (class "Default")
      (node (ref "U3") (pin "10") (pinfunction "NC_10") (pintype "no_connect"))
    )
    (net (code "59") (name "unconnected-(X1-PadID)") (class "Default")
      (node (ref "X1") (pin "ID") (pinfunction "ID_ID") (pintype "bidirectional"))
    )
  )
)
